# circuit.net
KiCad netlist of a schematic drawn in EAGLE
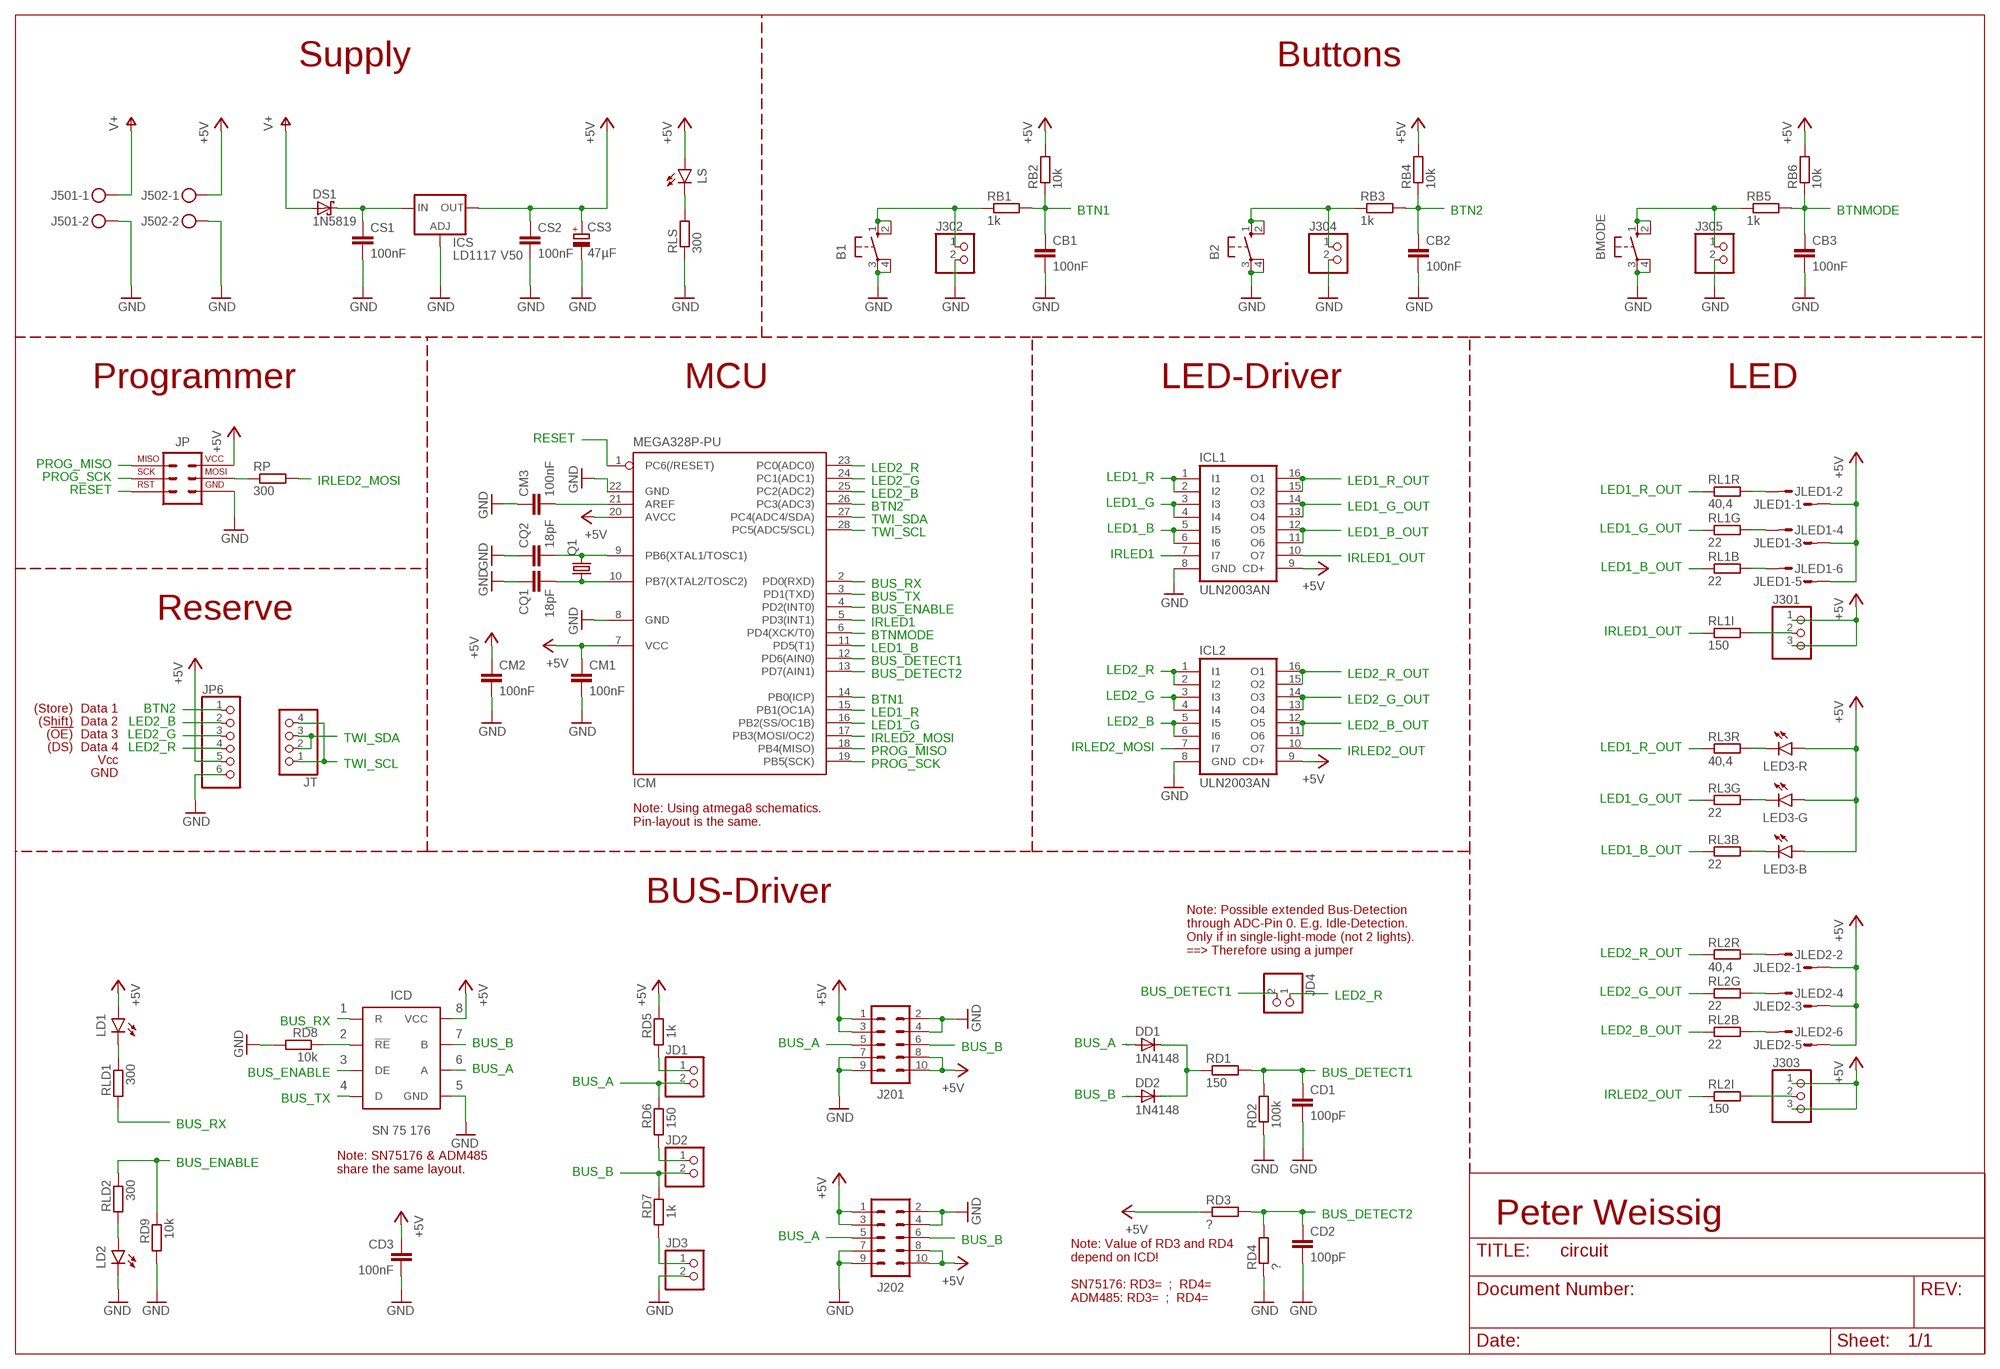
[diagram p0: schematic, sheet 1]

(export (version "E")
  (design (tool "Eeschema 10.0.6"))
  (components
    (comp (ref "B1")
      (value "10-XX")
      (footprint "eagle-import:B3F-10XX")
      (fields (field (name "MPN") "B3F-1000"))
      (libsource (lib "eagle-import") (part "10-XX"))
    )
    (comp (ref "B2")
      (value "10-XX")
      (footprint "eagle-import:B3F-10XX")
      (fields (field (name "MPN") "B3F-1000"))
      (libsource (lib "eagle-import") (part "10-XX"))
    )
    (comp (ref "BMODE")
      (value "10-XX")
      (footprint "eagle-import:B3F-10XX")
      (fields (field (name "MPN") "B3F-1000"))
      (libsource (lib "eagle-import") (part "10-XX"))
    )
    (comp (ref "CB1")
      (value "100nF")
      (footprint "eagle-import:C025-025X050")
      (libsource (lib "eagle-import") (part "C-EU025-025X050"))
    )
    (comp (ref "CB2")
      (value "100nF")
      (footprint "eagle-import:C025-025X050")
      (libsource (lib "eagle-import") (part "C-EU025-025X050"))
    )
    (comp (ref "CB3")
      (value "100nF")
      (footprint "eagle-import:C025-025X050")
      (libsource (lib "eagle-import") (part "C-EU025-025X050"))
    )
    (comp (ref "CD1")
      (value "100pF")
      (footprint "eagle-import:C025-025X050")
      (libsource (lib "eagle-import") (part "C-EU025-025X050"))
    )
    (comp (ref "CD2")
      (value "100pF")
      (footprint "eagle-import:C025-025X050")
      (libsource (lib "eagle-import") (part "C-EU025-025X050"))
    )
    (comp (ref "CD3")
      (value "100nF")
      (footprint "eagle-import:C025-025X050")
      (libsource (lib "eagle-import") (part "C-EU025-025X050"))
    )
    (comp (ref "CM1")
      (value "100nF")
      (footprint "eagle-import:C025-025X050")
      (libsource (lib "eagle-import") (part "C-EU025-025X050"))
    )
    (comp (ref "CM2")
      (value "100nF")
      (footprint "eagle-import:C025-025X050")
      (libsource (lib "eagle-import") (part "C-EU025-025X050"))
    )
    (comp (ref "CM3")
      (value "100nF")
      (footprint "eagle-import:C025-025X050")
      (libsource (lib "eagle-import") (part "C-EU025-025X050"))
    )
    (comp (ref "CQ1")
      (value "18pF")
      (footprint "eagle-import:C025-025X050")
      (libsource (lib "eagle-import") (part "C-EU025-025X050"))
    )
    (comp (ref "CQ2")
      (value "18pF")
      (footprint "eagle-import:C025-025X050")
      (libsource (lib "eagle-import") (part "C-EU025-025X050"))
    )
    (comp (ref "CS1")
      (value "100nF")
      (footprint "eagle-import:C025-025X050")
      (libsource (lib "eagle-import") (part "C-EU025-025X050"))
    )
    (comp (ref "CS2")
      (value "100nF")
      (footprint "eagle-import:C025-025X050")
      (libsource (lib "eagle-import") (part "C-EU025-025X050"))
    )
    (comp (ref "CS3")
      (value "47µF")
      (footprint "eagle-import:E2-5")
      (libsource (lib "eagle-import") (part "CPOL-EUE2-5"))
    )
    (comp (ref "DD1")
      (value "1N4148")
      (footprint "eagle-import:DO35-7")
      (libsource (lib "eagle-import") (part "1N4148DO35-7"))
    )
    (comp (ref "DD2")
      (value "1N4148")
      (footprint "eagle-import:DO35-7")
      (libsource (lib "eagle-import") (part "1N4148DO35-7"))
    )
    (comp (ref "DS1")
      (value "1N5819")
      (footprint "eagle-import:DO41-7.6")
      (libsource (lib "eagle-import") (part "1N5819-B"))
    )
    (comp (ref "ICD")
      (value "DRIVER_RS485")
      (footprint "eagle-import:IC_DIL08")
      (libsource (lib "eagle-import") (part "DRIVER_RS485"))
    )
    (comp (ref "ICL1")
      (value "ULN2003AN")
      (footprint "eagle-import:DIL16")
      (libsource (lib "eagle-import") (part "ULN2003AN"))
    )
    (comp (ref "ICL2")
      (value "ULN2003AN")
      (footprint "eagle-import:DIL16")
      (libsource (lib "eagle-import") (part "ULN2003AN"))
    )
    (comp (ref "ICM")
      (value "MEGA328P-PU")
      (footprint "eagle-import:DIL28-3")
      (libsource (lib "eagle-import") (part "MEGA8-P"))
    )
    (comp (ref "ICS")
      (value "LD1117 V50")
      (footprint "eagle-import:TO220L1")
      (libsource (lib "eagle-import") (part "LD117A?V50"))
    )
    (comp (ref "J201")
      (value "STECKER_WANNE_10")
      (footprint "eagle-import:STECKER_WANNE_10")
      (libsource (lib "eagle-import") (part "STECKER_WANNE_10"))
    )
    (comp (ref "J202")
      (value "STECKER_WANNE_10")
      (footprint "eagle-import:STECKER_WANNE_10")
      (libsource (lib "eagle-import") (part "STECKER_WANNE_10"))
    )
    (comp (ref "J301")
      (value "PINHD-1X3")
      (footprint "eagle-import:1X03")
      (libsource (lib "eagle-import") (part "PINHD-1X3"))
    )
    (comp (ref "J302")
      (value "PINHD-1X2")
      (footprint "eagle-import:1X02")
      (libsource (lib "eagle-import") (part "PINHD-1X2"))
    )
    (comp (ref "J303")
      (value "PINHD-1X3")
      (footprint "eagle-import:1X03")
      (libsource (lib "eagle-import") (part "PINHD-1X3"))
    )
    (comp (ref "J304")
      (value "PINHD-1X2")
      (footprint "eagle-import:1X02")
      (libsource (lib "eagle-import") (part "PINHD-1X2"))
    )
    (comp (ref "J305")
      (value "PINHD-1X2")
      (footprint "eagle-import:1X02")
      (libsource (lib "eagle-import") (part "PINHD-1X2"))
    )
    (comp (ref "J501")
      (value "STECKER_SPG_2")
      (footprint "eagle-import:STECKER_SPG_2")
      (libsource (lib "eagle-import") (part "STECKER_SPG_2"))
    )
    (comp (ref "J502")
      (value "STECKER_SPG_2")
      (footprint "eagle-import:STECKER_SPG_2")
      (libsource (lib "eagle-import") (part "STECKER_SPG_2"))
    )
    (comp (ref "JD1")
      (value "PINHD-1X2")
      (footprint "eagle-import:1X02")
      (libsource (lib "eagle-import") (part "PINHD-1X2"))
    )
    (comp (ref "JD2")
      (value "PINHD-1X2")
      (footprint "eagle-import:1X02")
      (libsource (lib "eagle-import") (part "PINHD-1X2"))
    )
    (comp (ref "JD3")
      (value "PINHD-1X2")
      (footprint "eagle-import:1X02")
      (libsource (lib "eagle-import") (part "PINHD-1X2"))
    )
    (comp (ref "JD4")
      (value "PINHD-1X2")
      (footprint "eagle-import:1X02")
      (libsource (lib "eagle-import") (part "PINHD-1X2"))
    )
    (comp (ref "JLED1")
      (value "MICROMATCH-6")
      (footprint "eagle-import:MICROMATCH-6")
      (fields (field (name "MPN") "7-215464-6"))
      (libsource (lib "eagle-import") (part "MICROMATCH-6"))
    )
    (comp (ref "JLED2")
      (value "MICROMATCH-6")
      (footprint "eagle-import:MICROMATCH-6")
      (fields (field (name "MPN") "7-215464-6"))
      (libsource (lib "eagle-import") (part "MICROMATCH-6"))
    )
    (comp (ref "JP")
      (value "STECKER_ISP_6")
      (footprint "eagle-import:STECKER_WANNE_6")
      (libsource (lib "eagle-import") (part "STECKER_ISP_6"))
    )
    (comp (ref "JP6")
      (value "PINHD-1X6/90")
      (footprint "eagle-import:1X06_90")
      (libsource (lib "eagle-import") (part "PINHD-1X6/90"))
    )
    (comp (ref "JT")
      (value "PINHD-1X4")
      (footprint "eagle-import:1X04")
      (libsource (lib "eagle-import") (part "PINHD-1X4"))
    )
    (comp (ref "LD1")
      (value "LED-3MM")
      (footprint "eagle-import:LED_3MM")
      (libsource (lib "eagle-import") (part "LED-3MM"))
    )
    (comp (ref "LD2")
      (value "LED-3MM")
      (footprint "eagle-import:LED_3MM")
      (libsource (lib "eagle-import") (part "LED-3MM"))
    )
    (comp (ref "LED3")
      (value "LED_3X")
      (footprint "eagle-import:LED_TOP_PLCC6")
      (libsource (lib "eagle-import") (part "LED_3X"))
    )
    (comp (ref "LS")
      (value "LED-3MM")
      (footprint "eagle-import:LED_3MM")
      (libsource (lib "eagle-import") (part "LED-3MM"))
    )
    (comp (ref "Q1")
      (value "CRYSTALHC49U70")
      (footprint "eagle-import:HC49U70")
      (libsource (lib "eagle-import") (part "CRYSTALHC49U70"))
    )
    (comp (ref "RB1")
      (value "1k")
      (footprint "eagle-import:0207_10")
      (libsource (lib "eagle-import") (part "R-EU_0207/10"))
    )
    (comp (ref "RB2")
      (value "10k")
      (footprint "eagle-import:0207_10")
      (libsource (lib "eagle-import") (part "R-EU_0207/10"))
    )
    (comp (ref "RB3")
      (value "1k")
      (footprint "eagle-import:0207_10")
      (libsource (lib "eagle-import") (part "R-EU_0207/10"))
    )
    (comp (ref "RB4")
      (value "10k")
      (footprint "eagle-import:0207_10")
      (libsource (lib "eagle-import") (part "R-EU_0207/10"))
    )
    (comp (ref "RB5")
      (value "1k")
      (footprint "eagle-import:0207_10")
      (libsource (lib "eagle-import") (part "R-EU_0207/10"))
    )
    (comp (ref "RB6")
      (value "10k")
      (footprint "eagle-import:0207_10")
      (libsource (lib "eagle-import") (part "R-EU_0207/10"))
    )
    (comp (ref "RD1")
      (value "150")
      (footprint "eagle-import:0207_10")
      (libsource (lib "eagle-import") (part "R-EU_0207/10"))
    )
    (comp (ref "RD2")
      (value "100k")
      (footprint "eagle-import:0207_10")
      (libsource (lib "eagle-import") (part "R-EU_0207/10"))
    )
    (comp (ref "RD3")
      (value "?")
      (footprint "eagle-import:0207_10")
      (libsource (lib "eagle-import") (part "R-EU_0207/10"))
    )
    (comp (ref "RD4")
      (value "?")
      (footprint "eagle-import:0207_10")
      (libsource (lib "eagle-import") (part "R-EU_0207/10"))
    )
    (comp (ref "RD5")
      (value "1k")
      (footprint "eagle-import:0207_10")
      (libsource (lib "eagle-import") (part "R-EU_0207/10"))
    )
    (comp (ref "RD6")
      (value "150")
      (footprint "eagle-import:0207_10")
      (libsource (lib "eagle-import") (part "R-EU_0207/10"))
    )
    (comp (ref "RD7")
      (value "1k")
      (footprint "eagle-import:0207_10")
      (libsource (lib "eagle-import") (part "R-EU_0207/10"))
    )
    (comp (ref "RD8")
      (value "10k")
      (footprint "eagle-import:0207_10")
      (libsource (lib "eagle-import") (part "R-EU_0207/10"))
    )
    (comp (ref "RD9")
      (value "10k")
      (footprint "eagle-import:0207_10")
      (libsource (lib "eagle-import") (part "R-EU_0207/10"))
    )
    (comp (ref "RL1B")
      (value "22")
      (footprint "eagle-import:0207_10")
      (libsource (lib "eagle-import") (part "R-EU_0207/10"))
    )
    (comp (ref "RL1G")
      (value "22")
      (footprint "eagle-import:0207_10")
      (libsource (lib "eagle-import") (part "R-EU_0207/10"))
    )
    (comp (ref "RL1I")
      (value "150")
      (footprint "eagle-import:0207_10")
      (libsource (lib "eagle-import") (part "R-EU_0207/10"))
    )
    (comp (ref "RL1R")
      (value "40,4")
      (footprint "eagle-import:0207_10")
      (libsource (lib "eagle-import") (part "R-EU_0207/10"))
    )
    (comp (ref "RL2B")
      (value "22")
      (footprint "eagle-import:0207_10")
      (libsource (lib "eagle-import") (part "R-EU_0207/10"))
    )
    (comp (ref "RL2G")
      (value "22")
      (footprint "eagle-import:0207_10")
      (libsource (lib "eagle-import") (part "R-EU_0207/10"))
    )
    (comp (ref "RL2I")
      (value "150")
      (footprint "eagle-import:0207_10")
      (libsource (lib "eagle-import") (part "R-EU_0207/10"))
    )
    (comp (ref "RL2R")
      (value "40,4")
      (footprint "eagle-import:0207_10")
      (libsource (lib "eagle-import") (part "R-EU_0207/10"))
    )
    (comp (ref "RL3B")
      (value "22")
      (footprint "eagle-import:0207_10")
      (libsource (lib "eagle-import") (part "R-EU_0207/10"))
    )
    (comp (ref "RL3G")
      (value "22")
      (footprint "eagle-import:0207_10")
      (libsource (lib "eagle-import") (part "R-EU_0207/10"))
    )
    (comp (ref "RL3R")
      (value "40,4")
      (footprint "eagle-import:0207_10")
      (libsource (lib "eagle-import") (part "R-EU_0207/10"))
    )
    (comp (ref "RLD1")
      (value "300")
      (footprint "eagle-import:0207_10")
      (libsource (lib "eagle-import") (part "R-EU_0207/10"))
    )
    (comp (ref "RLD2")
      (value "300")
      (footprint "eagle-import:0207_10")
      (libsource (lib "eagle-import") (part "R-EU_0207/10"))
    )
    (comp (ref "RLS")
      (value "300")
      (footprint "eagle-import:0207_10")
      (libsource (lib "eagle-import") (part "R-EU_0207/10"))
    )
    (comp (ref "RP")
      (value "300")
      (footprint "eagle-import:0207_10")
      (libsource (lib "eagle-import") (part "R-EU_0207/10"))
    )
  )
  (nets
    (net (code "1") (name "+5V") (class "Default")
      (node (ref "CD3") (pin "1") (pinfunction "1_1") (pintype "passive"))
      (node (ref "CM1") (pin "1") (pinfunction "1_1") (pintype "passive"))
      (node (ref "CM2") (pin "1") (pinfunction "1_1") (pintype "passive"))
      (node (ref "CS2") (pin "1") (pinfunction "1_1") (pintype "passive"))
      (node (ref "CS3") (pin "+") (pinfunction "+_+") (pintype "passive"))
      (node (ref "ICD") (pin "8") (pinfunction "VCC_8") (pintype "power_in"))
      (node (ref "ICL1") (pin "9") (pinfunction "CD+_9") (pintype "passive"))
      (node (ref "ICL2") (pin "9") (pinfunction "CD+_9") (pintype "passive"))
      (node (ref "ICM") (pin "20") (pinfunction "AVCC_20") (pintype "power_in"))
      (node (ref "ICM") (pin "7") (pinfunction "VCC_7") (pintype "power_in"))
      (node (ref "ICS") (pin "2") (pinfunction "OUT_2") (pintype "passive"))
      (node (ref "J201") (pin "1") (pinfunction "1_1") (pintype "passive"))
      (node (ref "J201") (pin "10") (pinfunction "10_10") (pintype "passive"))
      (node (ref "J201") (pin "3") (pinfunction "3_3") (pintype "passive"))
      (node (ref "J201") (pin "8") (pinfunction "8_8") (pintype "passive"))
      (node (ref "J202") (pin "1") (pinfunction "1_1") (pintype "passive"))
      (node (ref "J202") (pin "10") (pinfunction "10_10") (pintype "passive"))
      (node (ref "J202") (pin "3") (pinfunction "3_3") (pintype "passive"))
      (node (ref "J202") (pin "8") (pinfunction "8_8") (pintype "passive"))
      (node (ref "J301") (pin "1") (pinfunction "1_1") (pintype "passive"))
      (node (ref "J301") (pin "3") (pinfunction "3_3") (pintype "passive"))
      (node (ref "J303") (pin "1") (pinfunction "1_1") (pintype "passive"))
      (node (ref "J303") (pin "3") (pinfunction "3_3") (pintype "passive"))
      (node (ref "J502") (pin "1") (pinfunction "KL_1") (pintype "passive"))
      (node (ref "JLED1") (pin "1") (pinfunction "S_1") (pintype "passive"))
      (node (ref "JLED1") (pin "3") (pinfunction "S_3") (pintype "passive"))
      (node (ref "JLED1") (pin "5") (pinfunction "S_5") (pintype "passive"))
      (node (ref "JLED2") (pin "1") (pinfunction "S_1") (pintype "passive"))
      (node (ref "JLED2") (pin "3") (pinfunction "S_3") (pintype "passive"))
      (node (ref "JLED2") (pin "5") (pinfunction "S_5") (pintype "passive"))
      (node (ref "JP") (pin "2") (pinfunction "2_VCC_2") (pintype "passive"))
      (node (ref "JP6") (pin "5") (pinfunction "5_5") (pintype "passive"))
      (node (ref "LD1") (pin "A") (pinfunction "A_A") (pintype "passive"))
      (node (ref "LED3") (pin "1") (pinfunction "A_1") (pintype "passive"))
      (node (ref "LED3") (pin "3") (pinfunction "A_3") (pintype "passive"))
      (node (ref "LED3") (pin "4") (pinfunction "A_4") (pintype "passive"))
      (node (ref "LS") (pin "A") (pinfunction "A_A") (pintype "passive"))
      (node (ref "RB2") (pin "2") (pinfunction "2_2") (pintype "passive"))
      (node (ref "RB4") (pin "2") (pinfunction "2_2") (pintype "passive"))
      (node (ref "RB6") (pin "2") (pinfunction "2_2") (pintype "passive"))
      (node (ref "RD3") (pin "1") (pinfunction "1_1") (pintype "passive"))
      (node (ref "RD5") (pin "2") (pinfunction "2_2") (pintype "passive"))
    )
    (net (code "2") (name "/BTN1") (class "Default")
      (node (ref "CB1") (pin "1") (pinfunction "1_1") (pintype "passive"))
      (node (ref "ICM") (pin "14") (pinfunction "PB0(ICP)_14") (pintype "bidirectional"))
      (node (ref "RB1") (pin "2") (pinfunction "2_2") (pintype "passive"))
      (node (ref "RB2") (pin "1") (pinfunction "1_1") (pintype "passive"))
    )
    (net (code "3") (name "/BTN2") (class "Default")
      (node (ref "CB2") (pin "1") (pinfunction "1_1") (pintype "passive"))
      (node (ref "ICM") (pin "26") (pinfunction "PC3(ADC3)_26") (pintype "bidirectional"))
      (node (ref "JP6") (pin "1") (pinfunction "1_1") (pintype "passive"))
      (node (ref "RB3") (pin "2") (pinfunction "2_2") (pintype "passive"))
      (node (ref "RB4") (pin "1") (pinfunction "1_1") (pintype "passive"))
    )
    (net (code "4") (name "/BTNMODE") (class "Default")
      (node (ref "CB3") (pin "1") (pinfunction "1_1") (pintype "passive"))
      (node (ref "ICM") (pin "6") (pinfunction "PD4(XCK/T0)_6") (pintype "bidirectional"))
      (node (ref "RB5") (pin "2") (pinfunction "2_2") (pintype "passive"))
      (node (ref "RB6") (pin "1") (pinfunction "1_1") (pintype "passive"))
    )
    (net (code "5") (name "/BUS_A") (class "Default")
      (node (ref "DD1") (pin "A") (pinfunction "A_A") (pintype "passive"))
      (node (ref "ICD") (pin "6") (pinfunction "A_6") (pintype "bidirectional"))
      (node (ref "J201") (pin "5") (pinfunction "5_5") (pintype "passive"))
      (node (ref "J202") (pin "5") (pinfunction "5_5") (pintype "passive"))
      (node (ref "JD1") (pin "2") (pinfunction "2_2") (pintype "passive"))
      (node (ref "RD6") (pin "2") (pinfunction "2_2") (pintype "passive"))
    )
    (net (code "6") (name "/BUS_B") (class "Default")
      (node (ref "DD2") (pin "A") (pinfunction "A_A") (pintype "passive"))
      (node (ref "ICD") (pin "7") (pinfunction "B_7") (pintype "bidirectional"))
      (node (ref "J201") (pin "6") (pinfunction "6_6") (pintype "passive"))
      (node (ref "J202") (pin "6") (pinfunction "6_6") (pintype "passive"))
      (node (ref "JD2") (pin "2") (pinfunction "2_2") (pintype "passive"))
      (node (ref "RD7") (pin "2") (pinfunction "2_2") (pintype "passive"))
    )
    (net (code "7") (name "/BUS_DETECT1") (class "Default")
      (node (ref "CD1") (pin "1") (pinfunction "1_1") (pintype "passive"))
      (node (ref "ICM") (pin "12") (pinfunction "PD6(AIN0)_12") (pintype "bidirectional"))
      (node (ref "JD4") (pin "2") (pinfunction "2_2") (pintype "passive"))
      (node (ref "RD1") (pin "2") (pinfunction "2_2") (pintype "passive"))
      (node (ref "RD2") (pin "2") (pinfunction "2_2") (pintype "passive"))
    )
    (net (code "8") (name "/BUS_DETECT2") (class "Default")
      (node (ref "CD2") (pin "1") (pinfunction "1_1") (pintype "passive"))
      (node (ref "ICM") (pin "13") (pinfunction "PD7(AIN1)_13") (pintype "bidirectional"))
      (node (ref "RD3") (pin "2") (pinfunction "2_2") (pintype "passive"))
      (node (ref "RD4") (pin "2") (pinfunction "2_2") (pintype "passive"))
    )
    (net (code "9") (name "/BUS_ENABLE") (class "Default")
      (node (ref "ICD") (pin "3") (pinfunction "DE_3") (pintype "input"))
      (node (ref "ICM") (pin "4") (pinfunction "PD2(INT0)_4") (pintype "bidirectional"))
      (node (ref "RD9") (pin "1") (pinfunction "1_1") (pintype "passive"))
      (node (ref "RLD2") (pin "1") (pinfunction "1_1") (pintype "passive"))
    )
    (net (code "10") (name "/BUS_RX") (class "Default")
      (node (ref "ICD") (pin "1") (pinfunction "R_1") (pintype "output"))
      (node (ref "ICM") (pin "2") (pinfunction "PD0(RXD)_2") (pintype "bidirectional"))
      (node (ref "RLD1") (pin "2") (pinfunction "2_2") (pintype "passive"))
    )
    (net (code "11") (name "/BUS_TX") (class "Default")
      (node (ref "ICD") (pin "4") (pinfunction "D_4") (pintype "input"))
      (node (ref "ICM") (pin "3") (pinfunction "PD1(TXD)_3") (pintype "bidirectional"))
    )
    (net (code "12") (name "/IRLED1") (class "Default")
      (node (ref "ICL1") (pin "7") (pinfunction "I7_7") (pintype "input"))
      (node (ref "ICM") (pin "5") (pinfunction "PD3(INT1)_5") (pintype "bidirectional"))
    )
    (net (code "13") (name "/IRLED1_OUT") (class "Default")
      (node (ref "ICL1") (pin "10") (pinfunction "O7_10") (pintype "open_collector"))
      (node (ref "RL1I") (pin "1") (pinfunction "1_1") (pintype "passive"))
    )
    (net (code "14") (name "/IRLED2_MOSI") (class "Default")
      (node (ref "ICL2") (pin "7") (pinfunction "I7_7") (pintype "input"))
      (node (ref "ICM") (pin "17") (pinfunction "PB3(MOSI/OC2)_17") (pintype "bidirectional"))
      (node (ref "RP") (pin "2") (pinfunction "2_2") (pintype "passive"))
    )
    (net (code "15") (name "/IRLED2_OUT") (class "Default")
      (node (ref "ICL2") (pin "10") (pinfunction "O7_10") (pintype "open_collector"))
      (node (ref "RL2I") (pin "1") (pinfunction "1_1") (pintype "passive"))
    )
    (net (code "16") (name "/LED1_B") (class "Default")
      (node (ref "ICL1") (pin "5") (pinfunction "I5_5") (pintype "input"))
      (node (ref "ICL1") (pin "6") (pinfunction "I6_6") (pintype "input"))
      (node (ref "ICM") (pin "11") (pinfunction "PD5(T1)_11") (pintype "bidirectional"))
    )
    (net (code "17") (name "/LED1_B_OUT") (class "Default")
      (node (ref "ICL1") (pin "11") (pinfunction "O6_11") (pintype "open_collector"))
      (node (ref "ICL1") (pin "12") (pinfunction "O5_12") (pintype "open_collector"))
      (node (ref "RL1B") (pin "1") (pinfunction "1_1") (pintype "passive"))
      (node (ref "RL3B") (pin "1") (pinfunction "1_1") (pintype "passive"))
    )
    (net (code "18") (name "/LED1_G") (class "Default")
      (node (ref "ICL1") (pin "3") (pinfunction "I3_3") (pintype "input"))
      (node (ref "ICL1") (pin "4") (pinfunction "I4_4") (pintype "input"))
      (node (ref "ICM") (pin "16") (pinfunction "PB2(SS/OC1B)_16") (pintype "bidirectional"))
    )
    (net (code "19") (name "/LED1_G_OUT") (class "Default")
      (node (ref "ICL1") (pin "13") (pinfunction "O4_13") (pintype "open_collector"))
      (node (ref "ICL1") (pin "14") (pinfunction "O3_14") (pintype "open_collector"))
      (node (ref "RL1G") (pin "1") (pinfunction "1_1") (pintype "passive"))
      (node (ref "RL3G") (pin "1") (pinfunction "1_1") (pintype "passive"))
    )
    (net (code "20") (name "/LED1_R") (class "Default")
      (node (ref "ICL1") (pin "1") (pinfunction "I1_1") (pintype "input"))
      (node (ref "ICL1") (pin "2") (pinfunction "I2_2") (pintype "input"))
      (node (ref "ICM") (pin "15") (pinfunction "PB1(OC1A)_15") (pintype "bidirectional"))
    )
    (net (code "21") (name "/LED1_R_OUT") (class "Default")
      (node (ref "ICL1") (pin "15") (pinfunction "O2_15") (pintype "open_collector"))
      (node (ref "ICL1") (pin "16") (pinfunction "O1_16") (pintype "open_collector"))
      (node (ref "RL1R") (pin "1") (pinfunction "1_1") (pintype "passive"))
      (node (ref "RL3R") (pin "1") (pinfunction "1_1") (pintype "passive"))
    )
    (net (code "22") (name "/LED2_B") (class "Default")
      (node (ref "ICL2") (pin "5") (pinfunction "I5_5") (pintype "input"))
      (node (ref "ICL2") (pin "6") (pinfunction "I6_6") (pintype "input"))
      (node (ref "ICM") (pin "25") (pinfunction "PC2(ADC2)_25") (pintype "bidirectional"))
      (node (ref "JP6") (pin "2") (pinfunction "2_2") (pintype "passive"))
    )
    (net (code "23") (name "/LED2_B_OUT") (class "Default")
      (node (ref "ICL2") (pin "11") (pinfunction "O6_11") (pintype "open_collector"))
      (node (ref "ICL2") (pin "12") (pinfunction "O5_12") (pintype "open_collector"))
      (node (ref "RL2B") (pin "1") (pinfunction "1_1") (pintype "passive"))
    )
    (net (code "24") (name "/LED2_G") (class "Default")
      (node (ref "ICL2") (pin "3") (pinfunction "I3_3") (pintype "input"))
      (node (ref "ICL2") (pin "4") (pinfunction "I4_4") (pintype "input"))
      (node (ref "ICM") (pin "24") (pinfunction "PC1(ADC1)_24") (pintype "bidirectional"))
      (node (ref "JP6") (pin "3") (pinfunction "3_3") (pintype "passive"))
    )
    (net (code "25") (name "/LED2_G_OUT") (class "Default")
      (node (ref "ICL2") (pin "13") (pinfunction "O4_13") (pintype "open_collector"))
      (node (ref "ICL2") (pin "14") (pinfunction "O3_14") (pintype "open_collector"))
      (node (ref "RL2G") (pin "1") (pinfunction "1_1") (pintype "passive"))
    )
    (net (code "26") (name "/LED2_R") (class "Default")
      (node (ref "ICL2") (pin "1") (pinfunction "I1_1") (pintype "input"))
      (node (ref "ICL2") (pin "2") (pinfunction "I2_2") (pintype "input"))
      (node (ref "ICM") (pin "23") (pinfunction "PC0(ADC0)_23") (pintype "bidirectional"))
      (node (ref "JD4") (pin "1") (pinfunction "1_1") (pintype "passive"))
      (node (ref "JP6") (pin "4") (pinfunction "4_4") (pintype "passive"))
    )
    (net (code "27") (name "/LED2_R_OUT") (class "Default")
      (node (ref "ICL2") (pin "15") (pinfunction "O2_15") (pintype "open_collector"))
      (node (ref "ICL2") (pin "16") (pinfunction "O1_16") (pintype "open_collector"))
      (node (ref "RL2R") (pin "1") (pinfunction "1_1") (pintype "passive"))
    )
    (net (code "28") (name "/PROG_MISO") (class "Default")
      (node (ref "ICM") (pin "18") (pinfunction "PB4(MISO)_18") (pintype "bidirectional"))
      (node (ref "JP") (pin "1") (pinfunction "1_MISO_1") (pintype "passive"))
    )
    (net (code "29") (name "/PROG_SCK") (class "Default")
      (node (ref "ICM") (pin "19") (pinfunction "PB5(SCK)_19") (pintype "bidirectional"))
      (node (ref "JP") (pin "3") (pinfunction "3_SCK_3") (pintype "passive"))
    )
    (net (code "30") (name "/RESET") (class "Default")
      (node (ref "ICM") (pin "1") (pinfunction "PC6(/RESET)_1") (pintype "bidirectional"))
      (node (ref "JP") (pin "5") (pinfunction "5_RST_5") (pintype "passive"))
    )
    (net (code "31") (name "/TWI_SCL") (class "Default")
      (node (ref "ICM") (pin "28") (pinfunction "PC5(ADC5/SCL)_28") (pintype "bidirectional"))
      (node (ref "JT") (pin "1") (pinfunction "1_1") (pintype "passive"))
      (node (ref "JT") (pin "4") (pinfunction "4_4") (pintype "passive"))
    )
    (net (code "32") (name "/TWI_SDA") (class "Default")
      (node (ref "ICM") (pin "27") (pinfunction "PC4(ADC4/SDA)_27") (pintype "bidirectional"))
      (node (ref "JT") (pin "2") (pinfunction "2_2") (pintype "passive"))
      (node (ref "JT") (pin "3") (pinfunction "3_3") (pintype "passive"))
    )
    (net (code "33") (name "GND") (class "Default")
      (node (ref "B1") (pin "3") (pinfunction "P_3") (pintype "passive"))
      (node (ref "B1") (pin "4") (pinfunction "P1_4") (pintype "passive"))
      (node (ref "B2") (pin "3") (pinfunction "P_3") (pintype "passive"))
      (node (ref "B2") (pin "4") (pinfunction "P1_4") (pintype "passive"))
      (node (ref "BMODE") (pin "3") (pinfunction "P_3") (pintype "passive"))
      (node (ref "BMODE") (pin "4") (pinfunction "P1_4") (pintype "passive"))
      (node (ref "CB1") (pin "2") (pinfunction "2_2") (pintype "passive"))
      (node (ref "CB2") (pin "2") (pinfunction "2_2") (pintype "passive"))
      (node (ref "CB3") (pin "2") (pinfunction "2_2") (pintype "passive"))
      (node (ref "CD1") (pin "2") (pinfunction "2_2") (pintype "passive"))
      (node (ref "CD2") (pin "2") (pinfunction "2_2") (pintype "passive"))
      (node (ref "CD3") (pin "2") (pinfunction "2_2") (pintype "passive"))
      (node (ref "CM1") (pin "2") (pinfunction "2_2") (pintype "passive"))
      (node (ref "CM2") (pin "2") (pinfunction "2_2") (pintype "passive"))
      (node (ref "CM3") (pin "1") (pinfunction "1_1") (pintype "passive"))
      (node (ref "CQ1") (pin "1") (pinfunction "1_1") (pintype "passive"))
      (node (ref "CQ2") (pin "1") (pinfunction "1_1") (pintype "passive"))
      (node (ref "CS1") (pin "2") (pinfunction "2_2") (pintype "passive"))
      (node (ref "CS2") (pin "2") (pinfunction "2_2") (pintype "passive"))
      (node (ref "CS3") (pin "-") (pinfunction "-_-") (pintype "passive"))
      (node (ref "ICD") (pin "5") (pinfunction "GND_5") (pintype "power_in"))
      (node (ref "ICL1") (pin "8") (pinfunction "GND_8") (pintype "power_in"))
      (node (ref "ICL2") (pin "8") (pinfunction "GND_8") (pintype "power_in"))
      (node (ref "ICM") (pin "22") (pinfunction "GND_22") (pintype "power_in"))
      (node (ref "ICM") (pin "8") (pinfunction "GND_8") (pintype "power_in"))
      (node (ref "ICS") (pin "1") (pinfunction "ADJ_1") (pintype "input"))
      (node (ref "J201") (pin "2") (pinfunction "2_2") (pintype "passive"))
      (node (ref "J201") (pin "4") (pinfunction "4_4") (pintype "passive"))
      (node (ref "J201") (pin "7") (pinfunction "7_7") (pintype "passive"))
      (node (ref "J201") (pin "9") (pinfunction "9_9") (pintype "passive"))
      (node (ref "J202") (pin "2") (pinfunction "2_2") (pintype "passive"))
      (node (ref "J202") (pin "4") (pinfunction "4_4") (pintype "passive"))
      (node (ref "J202") (pin "7") (pinfunction "7_7") (pintype "passive"))
      (node (ref "J202") (pin "9") (pinfunction "9_9") (pintype "passive"))
      (node (ref "J302") (pin "2") (pinfunction "2_2") (pintype "passive"))
      (node (ref "J304") (pin "2") (pinfunction "2_2") (pintype "passive"))
      (node (ref "J305") (pin "2") (pinfunction "2_2") (pintype "passive"))
      (node (ref "J501") (pin "2") (pinfunction "KL_2") (pintype "passive"))
      (node (ref "J502") (pin "2") (pinfunction "KL_2") (pintype "passive"))
      (node (ref "JD3") (pin "2") (pinfunction "2_2") (pintype "passive"))
      (node (ref "JP") (pin "6") (pinfunction "6_GND_6") (pintype "passive"))
      (node (ref "JP6") (pin "6") (pinfunction "6_6") (pintype "passive"))
      (node (ref "LD2") (pin "K") (pinfunction "C_K") (pintype "passive"))
      (node (ref "RD2") (pin "1") (pinfunction "1_1") (pintype "passive"))
      (node (ref "RD4") (pin "1") (pinfunction "1_1") (pintype "passive"))
      (node (ref "RD8") (pin "2") (pinfunction "2_2") (pintype "passive"))
      (node (ref "RD9") (pin "2") (pinfunction "2_2") (pintype "passive"))
      (node (ref "RLS") (pin "1") (pinfunction "1_1") (pintype "passive"))
    )
    (net (code "34") (name "Net-(B1-S)") (class "Default")
      (node (ref "B1") (pin "1") (pinfunction "S_1") (pintype "passive"))
      (node (ref "B1") (pin "2") (pinfunction "S1_2") (pintype "passive"))
      (node (ref "J302") (pin "1") (pinfunction "1_1") (pintype "passive"))
      (node (ref "RB1") (pin "1") (pinfunction "1_1") (pintype "passive"))
    )
    (net (code "35") (name "Net-(B2-S)") (class "Default")
      (node (ref "B2") (pin "1") (pinfunction "S_1") (pintype "passive"))
      (node (ref "B2") (pin "2") (pinfunction "S1_2") (pintype "passive"))
      (node (ref "J304") (pin "1") (pinfunction "1_1") (pintype "passive"))
      (node (ref "RB3") (pin "1") (pinfunction "1_1") (pintype "passive"))
    )
    (net (code "36") (name "Net-(BMODE-S)") (class "Default")
      (node (ref "BMODE") (pin "1") (pinfunction "S_1") (pintype "passive"))
      (node (ref "BMODE") (pin "2") (pinfunction "S1_2") (pintype "passive"))
      (node (ref "J305") (pin "1") (pinfunction "1_1") (pintype "passive"))
      (node (ref "RB5") (pin "1") (pinfunction "1_1") (pintype "passive"))
    )
    (net (code "37") (name "Net-(DD1-PadC)") (class "Default")
      (node (ref "DD1") (pin "C") (pinfunction "C_C") (pintype "passive"))
      (node (ref "DD2") (pin "C") (pinfunction "C_C") (pintype "passive"))
      (node (ref "RD1") (pin "1") (pinfunction "1_1") (pintype "passive"))
    )
    (net (code "38") (name "Net-(ICD-~{RE})") (class "Default")
      (node (ref "ICD") (pin "2") (pinfunction "~{RE}_2") (pintype "input"))
      (node (ref "RD8") (pin "1") (pinfunction "1_1") (pintype "passive"))
    )
    (net (code "39") (name "Net-(ICM-AREF)") (class "Default")
      (node (ref "CM3") (pin "2") (pinfunction "2_2") (pintype "passive"))
      (node (ref "ICM") (pin "21") (pinfunction "AREF_21") (pintype "passive"))
    )
    (net (code "40") (name "Net-(ICM-PB6(XTAL1{slash}TOSC1))") (class "Default")
      (node (ref "CQ2") (pin "2") (pinfunction "2_2") (pintype "passive"))
      (node (ref "ICM") (pin "9") (pinfunction "PB6(XTAL1/TOSC1)_9") (pintype "bidirectional"))
      (node (ref "Q1") (pin "2") (pinfunction "2_2") (pintype "passive"))
    )
    (net (code "41") (name "Net-(ICM-PB7(XTAL2{slash}TOSC2))") (class "Default")
      (node (ref "CQ1") (pin "2") (pinfunction "2_2") (pintype "passive"))
      (node (ref "ICM") (pin "10") (pinfunction "PB7(XTAL2/TOSC2)_10") (pintype "bidirectional"))
      (node (ref "Q1") (pin "1") (pinfunction "1_1") (pintype "passive"))
    )
    (net (code "42") (name "Net-(ICS-IN)") (class "Default")
      (node (ref "CS1") (pin "1") (pinfunction "1_1") (pintype "passive"))
      (node (ref "DS1") (pin "C") (pinfunction "C_C") (pintype "passive"))
      (node (ref "ICS") (pin "3") (pinfunction "IN_3") (pintype "input"))
    )
    (net (code "43") (name "Net-(J301-Pad2)") (class "Default")
      (node (ref "J301") (pin "2") (pinfunction "2_2") (pintype "passive"))
      (node (ref "RL1I") (pin "2") (pinfunction "2_2") (pintype "passive"))
    )
    (net (code "44") (name "Net-(J303-Pad2)") (class "Default")
      (node (ref "J303") (pin "2") (pinfunction "2_2") (pintype "passive"))
      (node (ref "RL2I") (pin "2") (pinfunction "2_2") (pintype "passive"))
    )
    (net (code "45") (name "Net-(JD1-Pad1)") (class "Default")
      (node (ref "JD1") (pin "1") (pinfunction "1_1") (pintype "passive"))
      (node (ref "RD5") (pin "1") (pinfunction "1_1") (pintype "passive"))
    )
    (net (code "46") (name "Net-(JD2-Pad1)") (class "Default")
      (node (ref "JD2") (pin "1") (pinfunction "1_1") (pintype "passive"))
      (node (ref "RD6") (pin "1") (pinfunction "1_1") (pintype "passive"))
    )
    (net (code "47") (name "Net-(JD3-Pad1)") (class "Default")
      (node (ref "JD3") (pin "1") (pinfunction "1_1") (pintype "passive"))
      (node (ref "RD7") (pin "1") (pinfunction "1_1") (pintype "passive"))
    )
    (net (code "48") (name "Net-(JLED1B-S)") (class "Default")
      (node (ref "JLED1") (pin "2") (pinfunction "S_2") (pintype "passive"))
      (node (ref "RL1R") (pin "2") (pinfunction "2_2") (pintype "passive"))
    )
    (net (code "49") (name "Net-(JLED1D-S)") (class "Default")
      (node (ref "JLED1") (pin "4") (pinfunction "S_4") (pintype "passive"))
      (node (ref "RL1G") (pin "2") (pinfunction "2_2") (pintype "passive"))
    )
    (net (code "50") (name "Net-(JLED1F-S)") (class "Default")
      (node (ref "JLED1") (pin "6") (pinfunction "S_6") (pintype "passive"))
      (node (ref "RL1B") (pin "2") (pinfunction "2_2") (pintype "passive"))
    )
    (net (code "51") (name "Net-(JLED2B-S)") (class "Default")
      (node (ref "JLED2") (pin "2") (pinfunction "S_2") (pintype "passive"))
      (node (ref "RL2R") (pin "2") (pinfunction "2_2") (pintype "passive"))
    )
    (net (code "52") (name "Net-(JLED2D-S)") (class "Default")
      (node (ref "JLED2") (pin "4") (pinfunction "S_4") (pintype "passive"))
      (node (ref "RL2G") (pin "2") (pinfunction "2_2") (pintype "passive"))
    )
    (net (code "53") (name "Net-(JLED2F-S)") (class "Default")
      (node (ref "JLED2") (pin "6") (pinfunction "S_6") (pintype "passive"))
      (node (ref "RL2B") (pin "2") (pinfunction "2_2") (pintype "passive"))
    )
    (net (code "54") (name "Net-(JP-4_MOSI)") (class "Default")
      (node (ref "JP") (pin "4") (pinfunction "4_MOSI_4") (pintype "passive"))
      (node (ref "RP") (pin "1") (pinfunction "1_1") (pintype "passive"))
    )
    (net (code "55") (name "Net-(LD1-C)") (class "Default")
      (node (ref "LD1") (pin "K") (pinfunction "C_K") (pintype "passive"))
      (node (ref "RLD1") (pin "1") (pinfunction "1_1") (pintype "passive"))
    )
    (net (code "56") (name "Net-(LD2-PadA)") (class "Default")
      (node (ref "LD2") (pin "A") (pinfunction "A_A") (pintype "passive"))
      (node (ref "RLD2") (pin "2") (pinfunction "2_2") (pintype "passive"))
    )
    (net (code "57") (name "Net-(LED3A-C)") (class "Default")
      (node (ref "LED3") (pin "5") (pinfunction "C_5") (pintype "passive"))
      (node (ref "RL3B") (pin "2") (pinfunction "2_2") (pintype "passive"))
    )
    (net (code "58") (name "Net-(LED3B-C)") (class "Default")
      (node (ref "LED3") (pin "2") (pinfunction "C_2") (pintype "passive"))
      (node (ref "RL3G") (pin "2") (pinfunction "2_2") (pintype "passive"))
    )
    (net (code "59") (name "Net-(LED3C-C)") (class "Default")
      (node (ref "LED3") (pin "6") (pinfunction "C_6") (pintype "passive"))
      (node (ref "RL3R") (pin "2") (pinfunction "2_2") (pintype "passive"))
    )
    (net (code "60") (name "Net-(LS-C)") (class "Default")
      (node (ref "LS") (pin "K") (pinfunction "C_K") (pintype "passive"))
      (node (ref "RLS") (pin "2") (pinfunction "2_2") (pintype "passive"))
    )
    (net (code "61") (name "V+") (class "Default")
      (node (ref "DS1") (pin "A") (pinfunction "A_A") (pintype "passive"))
      (node (ref "J501") (pin "1") (pinfunction "KL_1") (pintype "passive"))
    )
  )
)
